# nolleblink2013.net
KiCad netlist of a schematic drawn in EAGLE
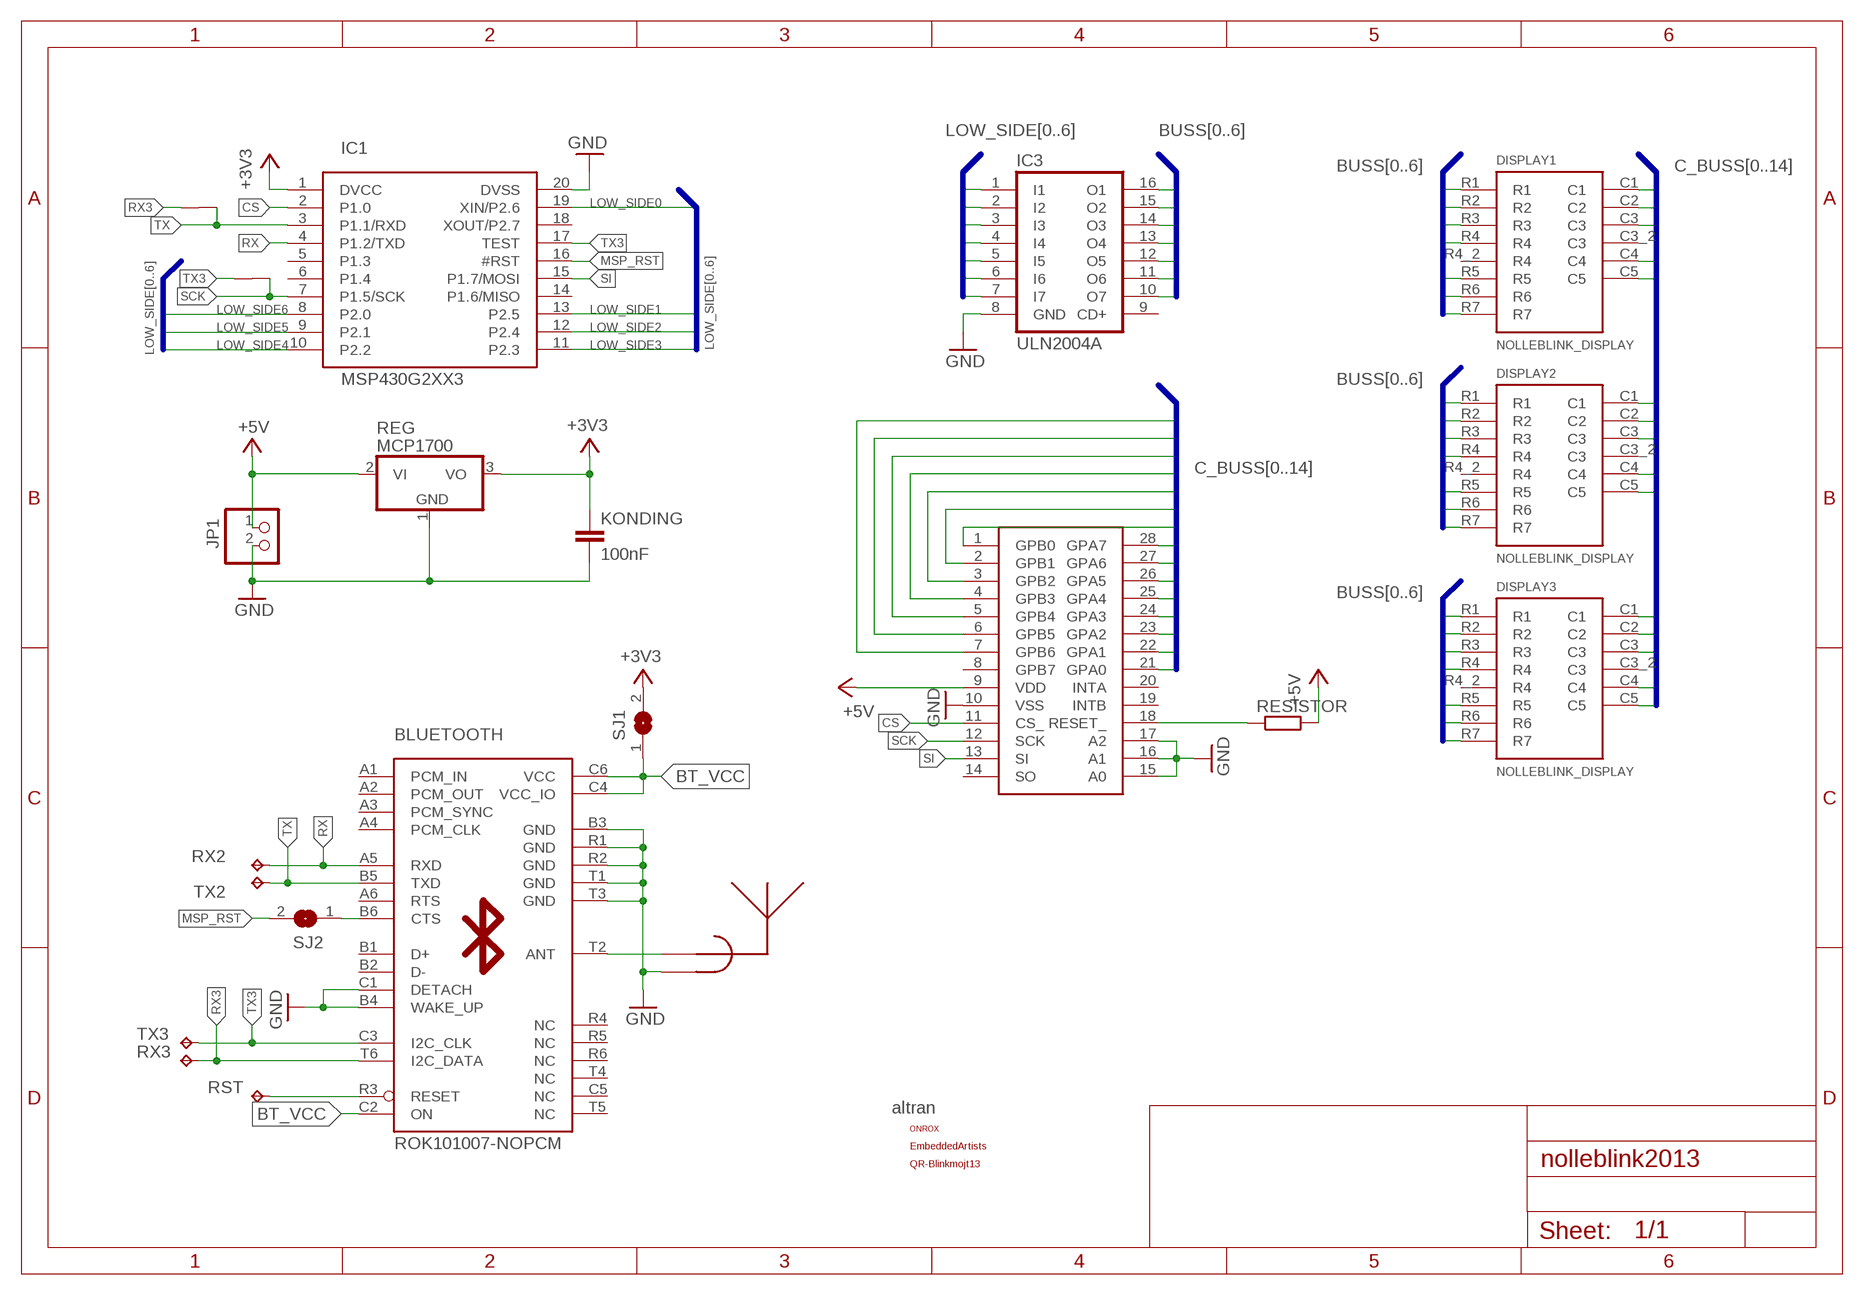
[diagram p0: schematic, sheet 1]

(export (version "E")
  (design (tool "Eeschema 10.0.6"))
  (components
    (comp (ref "BLUETOOTH")
      (value "ROK101007-NOPCM")
      (footprint "eagle-import:ROK101007_NOPCM")
      (libsource (lib "eagle-import") (part "ROK101007-NOPCM"))
    )
    (comp (ref "DISPLAY1")
      (value "NOLLEBLINK_DISPLAY")
      (footprint "eagle-import:KINGBRIGHT_TA12-11EWA")
      (libsource (lib "eagle-import") (part "NOLLEBLINK_DISPLAY"))
    )
    (comp (ref "DISPLAY2")
      (value "NOLLEBLINK_DISPLAY")
      (footprint "eagle-import:KINGBRIGHT_TA12-11EWA")
      (libsource (lib "eagle-import") (part "NOLLEBLINK_DISPLAY"))
    )
    (comp (ref "DISPLAY3")
      (value "NOLLEBLINK_DISPLAY")
      (footprint "eagle-import:KINGBRIGHT_TA12-11EWA")
      (libsource (lib "eagle-import") (part "NOLLEBLINK_DISPLAY"))
    )
    (comp (ref "IC1")
      (value "MSP430G2XX3")
      (footprint "eagle-import:N20")
      (libsource (lib "eagle-import") (part "MSP430G2XX3"))
    )
    (comp (ref "IC2")
      (value "MCPS23S17")
      (footprint "eagle-import:MCP23S17")
      (libsource (lib "eagle-import") (part "MCPS23S17"))
    )
    (comp (ref "IC3")
      (value "ULN2004A")
      (footprint "eagle-import:DIL16")
      (libsource (lib "eagle-import") (part "ULN2004AN"))
    )
    (comp (ref "JP1")
      (value "PINHD-1X2")
      (footprint "eagle-import:1X02")
      (libsource (lib "eagle-import") (part "PINHD-1X2"))
    )
    (comp (ref "KONDING")
      (value "100nF")
      (footprint "eagle-import:C050-030X075")
      (libsource (lib "eagle-import") (part "C-EU050-030X075"))
    )
    (comp (ref "REG")
      (value "MCP1700")
      (footprint "eagle-import:TO92_REGULATOR")
      (libsource (lib "eagle-import") (part "MCP_REGULATOR"))
    )
    (comp (ref "RESISTOR")
      (value "R-EU_0207/10")
      (footprint "eagle-import:0207_10")
      (libsource (lib "eagle-import") (part "R-EU_0207/10"))
    )
    (comp (ref "RST")
      (value "TPTP12SQ")
      (footprint "eagle-import:TP12SQ")
      (libsource (lib "eagle-import") (part "TPTP12SQ"))
    )
    (comp (ref "RX2")
      (value "TPTP20SQ")
      (footprint "eagle-import:TP20SQ")
      (libsource (lib "eagle-import") (part "TPTP20SQ"))
    )
    (comp (ref "RX3")
      (value "TPTP12SQ")
      (footprint "eagle-import:TP12SQ")
      (libsource (lib "eagle-import") (part "TPTP12SQ"))
    )
    (comp (ref "SJ1") (value "SJ") (footprint "eagle-import:SJ") (libsource (lib "eagle-import") (part "SJ")))
    (comp (ref "SJ2") (value "SJ") (footprint "eagle-import:SJ") (libsource (lib "eagle-import") (part "SJ")))
    (comp (ref "TX2")
      (value "TPTP20SQ")
      (footprint "eagle-import:TP20SQ")
      (libsource (lib "eagle-import") (part "TPTP20SQ"))
    )
    (comp (ref "TX3")
      (value "TPTP12SQ")
      (footprint "eagle-import:TP12SQ")
      (libsource (lib "eagle-import") (part "TPTP12SQ"))
    )
    (comp (ref "U$1")
      (value "ALTRAN")
      (footprint "eagle-import:ALTRAN")
      (libsource (lib "eagle-import") (part "ALTRAN"))
    )
    (comp (ref "U$2")
      (value "ONROX")
      (footprint "eagle-import:ONROX")
      (libsource (lib "eagle-import") (part "ONROX"))
    )
    (comp (ref "U$3")
      (value "INV_F_24")
      (footprint "eagle-import:INV_F_ANTENNA")
      (libsource (lib "eagle-import") (part "INV_F_24"))
    )
    (comp (ref "U$4")
      (value "EMBEDDEDARTISTS")
      (footprint "eagle-import:EMBEDDEDARTISTS")
      (libsource (lib "eagle-import") (part "EMBEDDEDARTISTS"))
    )
    (comp (ref "U$5")
      (value "JUNCTION")
      (footprint "eagle-import:JUNCTION")
      (libsource (lib "eagle-import") (part "JUNCTION"))
    )
    (comp (ref "U$6")
      (value "JUNCTION")
      (footprint "eagle-import:JUNCTION")
      (libsource (lib "eagle-import") (part "JUNCTION"))
    )
    (comp (ref "U$7")
      (value "BLINKMOJT13")
      (footprint "eagle-import:BLINKMOJT13")
      (libsource (lib "eagle-import") (part "BLINKMOJT13"))
    )
  )
  (nets
    (net (code "1") (name "+3V3") (class "Default")
      (node (ref "IC1") (pin "1") (pinfunction "DVCC_1") (pintype "bidirectional"))
      (node (ref "KONDING") (pin "1") (pinfunction "1_1") (pintype "passive"))
      (node (ref "REG") (pin "3") (pinfunction "VO_3") (pintype "passive"))
      (node (ref "SJ1") (pin "2") (pinfunction "2_2") (pintype "passive"))
    )
    (net (code "2") (name "+5V") (class "Default")
      (node (ref "IC2") (pin "9") (pinfunction "VDD_9") (pintype "bidirectional"))
      (node (ref "JP1") (pin "1") (pinfunction "1_1") (pintype "passive"))
      (node (ref "REG") (pin "2") (pinfunction "VI_2") (pintype "input"))
      (node (ref "RESISTOR") (pin "2") (pinfunction "2_2") (pintype "passive"))
    )
    (net (code "3") (name "/BUSS0") (class "Default")
      (node (ref "DISPLAY1") (pin "R1") (pinfunction "R1_R1") (pintype "bidirectional"))
      (node (ref "DISPLAY2") (pin "R1") (pinfunction "R1_R1") (pintype "bidirectional"))
      (node (ref "DISPLAY3") (pin "R1") (pinfunction "R1_R1") (pintype "bidirectional"))
      (node (ref "IC3") (pin "16") (pinfunction "O1_16") (pintype "open_collector"))
    )
    (net (code "4") (name "/BUSS1") (class "Default")
      (node (ref "DISPLAY1") (pin "R2") (pinfunction "R2_R2") (pintype "bidirectional"))
      (node (ref "DISPLAY2") (pin "R2") (pinfunction "R2_R2") (pintype "bidirectional"))
      (node (ref "DISPLAY3") (pin "R2") (pinfunction "R2_R2") (pintype "bidirectional"))
      (node (ref "IC3") (pin "15") (pinfunction "O2_15") (pintype "open_collector"))
    )
    (net (code "5") (name "/BUSS2") (class "Default")
      (node (ref "DISPLAY1") (pin "R3") (pinfunction "R3_R3") (pintype "bidirectional"))
      (node (ref "DISPLAY2") (pin "R3") (pinfunction "R3_R3") (pintype "bidirectional"))
      (node (ref "DISPLAY3") (pin "R3") (pinfunction "R3_R3") (pintype "bidirectional"))
      (node (ref "IC3") (pin "14") (pinfunction "O3_14") (pintype "open_collector"))
    )
    (net (code "6") (name "/BUSS3") (class "Default")
      (node (ref "DISPLAY1") (pin "R4") (pinfunction "R4_R4") (pintype "bidirectional"))
      (node (ref "DISPLAY2") (pin "R4") (pinfunction "R4_R4") (pintype "bidirectional"))
      (node (ref "DISPLAY3") (pin "R4") (pinfunction "R4_R4") (pintype "bidirectional"))
      (node (ref "IC3") (pin "13") (pinfunction "O4_13") (pintype "open_collector"))
    )
    (net (code "7") (name "/BUSS4") (class "Default")
      (node (ref "DISPLAY1") (pin "R5") (pinfunction "R5_R5") (pintype "bidirectional"))
      (node (ref "DISPLAY2") (pin "R5") (pinfunction "R5_R5") (pintype "bidirectional"))
      (node (ref "DISPLAY3") (pin "R5") (pinfunction "R5_R5") (pintype "bidirectional"))
      (node (ref "IC3") (pin "12") (pinfunction "O5_12") (pintype "open_collector"))
    )
    (net (code "8") (name "/BUSS5") (class "Default")
      (node (ref "DISPLAY1") (pin "R6") (pinfunction "R6_R6") (pintype "bidirectional"))
      (node (ref "DISPLAY2") (pin "R6") (pinfunction "R6_R6") (pintype "bidirectional"))
      (node (ref "DISPLAY3") (pin "R6") (pinfunction "R6_R6") (pintype "bidirectional"))
      (node (ref "IC3") (pin "11") (pinfunction "O6_11") (pintype "open_collector"))
    )
    (net (code "9") (name "/BUSS6") (class "Default")
      (node (ref "DISPLAY1") (pin "R7") (pinfunction "R7_R7") (pintype "bidirectional"))
      (node (ref "DISPLAY2") (pin "R7") (pinfunction "R7_R7") (pintype "bidirectional"))
      (node (ref "DISPLAY3") (pin "R7") (pinfunction "R7_R7") (pintype "bidirectional"))
      (node (ref "IC3") (pin "10") (pinfunction "O7_10") (pintype "open_collector"))
    )
    (net (code "11") (name "/C_BUSS0") (class "Default")
      (node (ref "DISPLAY1") (pin "C1") (pinfunction "C1_C1") (pintype "bidirectional"))
      (node (ref "IC2") (pin "21") (pinfunction "GPA0_21") (pintype "bidirectional"))
    )
    (net (code "12") (name "/C_BUSS1") (class "Default")
      (node (ref "DISPLAY1") (pin "C2") (pinfunction "C2_C2") (pintype "bidirectional"))
      (node (ref "IC2") (pin "22") (pinfunction "GPA1_22") (pintype "bidirectional"))
    )
    (net (code "13") (name "/C_BUSS2") (class "Default")
      (node (ref "DISPLAY1") (pin "C3") (pinfunction "C3_C3") (pintype "bidirectional"))
      (node (ref "IC2") (pin "23") (pinfunction "GPA2_23") (pintype "bidirectional"))
    )
    (net (code "14") (name "/C_BUSS3") (class "Default")
      (node (ref "DISPLAY1") (pin "C4") (pinfunction "C4_C4") (pintype "bidirectional"))
      (node (ref "IC2") (pin "24") (pinfunction "GPA3_24") (pintype "bidirectional"))
    )
    (net (code "15") (name "/C_BUSS4") (class "Default")
      (node (ref "DISPLAY1") (pin "C5") (pinfunction "C5_C5") (pintype "bidirectional"))
      (node (ref "IC2") (pin "25") (pinfunction "GPA4_25") (pintype "bidirectional"))
    )
    (net (code "16") (name "/C_BUSS5") (class "Default")
      (node (ref "DISPLAY2") (pin "C1") (pinfunction "C1_C1") (pintype "bidirectional"))
      (node (ref "IC2") (pin "26") (pinfunction "GPA5_26") (pintype "bidirectional"))
    )
    (net (code "17") (name "/C_BUSS6") (class "Default")
      (node (ref "DISPLAY2") (pin "C2") (pinfunction "C2_C2") (pintype "bidirectional"))
      (node (ref "IC2") (pin "27") (pinfunction "GPA6_27") (pintype "bidirectional"))
    )
    (net (code "18") (name "/C_BUSS7") (class "Default")
      (node (ref "DISPLAY2") (pin "C3") (pinfunction "C3_C3") (pintype "bidirectional"))
      (node (ref "IC2") (pin "28") (pinfunction "GPA7_28") (pintype "bidirectional"))
    )
    (net (code "19") (name "/C_BUSS8") (class "Default")
      (node (ref "DISPLAY2") (pin "C4") (pinfunction "C4_C4") (pintype "bidirectional"))
      (node (ref "IC2") (pin "1") (pinfunction "GPB0_1") (pintype "bidirectional"))
    )
    (net (code "20") (name "/C_BUSS9") (class "Default")
      (node (ref "DISPLAY2") (pin "C5") (pinfunction "C5_C5") (pintype "bidirectional"))
      (node (ref "IC2") (pin "2") (pinfunction "GPB1_2") (pintype "bidirectional"))
    )
    (net (code "21") (name "/C_BUSS10") (class "Default")
      (node (ref "DISPLAY3") (pin "C1") (pinfunction "C1_C1") (pintype "bidirectional"))
      (node (ref "IC2") (pin "3") (pinfunction "GPB2_3") (pintype "bidirectional"))
    )
    (net (code "22") (name "/C_BUSS11") (class "Default")
      (node (ref "DISPLAY3") (pin "C2") (pinfunction "C2_C2") (pintype "bidirectional"))
      (node (ref "IC2") (pin "4") (pinfunction "GPB3_4") (pintype "bidirectional"))
    )
    (net (code "23") (name "/C_BUSS12") (class "Default")
      (node (ref "DISPLAY3") (pin "C3") (pinfunction "C3_C3") (pintype "bidirectional"))
      (node (ref "IC2") (pin "5") (pinfunction "GPB4_5") (pintype "bidirectional"))
    )
    (net (code "24") (name "/C_BUSS13") (class "Default")
      (node (ref "DISPLAY3") (pin "C4") (pinfunction "C4_C4") (pintype "bidirectional"))
      (node (ref "IC2") (pin "6") (pinfunction "GPB5_6") (pintype "bidirectional"))
    )
    (net (code "25") (name "/C_BUSS14") (class "Default")
      (node (ref "DISPLAY3") (pin "C5") (pinfunction "C5_C5") (pintype "bidirectional"))
      (node (ref "IC2") (pin "7") (pinfunction "GPB6_7") (pintype "bidirectional"))
    )
    (net (code "27") (name "/LOW_SIDE0") (class "Default")
      (node (ref "IC1") (pin "19") (pinfunction "XIN/P2.6_19") (pintype "bidirectional"))
      (node (ref "IC3") (pin "7") (pinfunction "I7_7") (pintype "input"))
    )
    (net (code "28") (name "/LOW_SIDE1") (class "Default")
      (node (ref "IC1") (pin "13") (pinfunction "P2.5_13") (pintype "bidirectional"))
      (node (ref "IC3") (pin "6") (pinfunction "I6_6") (pintype "input"))
    )
    (net (code "29") (name "/LOW_SIDE2") (class "Default")
      (node (ref "IC1") (pin "12") (pinfunction "P2.4_12") (pintype "bidirectional"))
      (node (ref "IC3") (pin "5") (pinfunction "I5_5") (pintype "input"))
    )
    (net (code "30") (name "/LOW_SIDE3") (class "Default")
      (node (ref "IC1") (pin "11") (pinfunction "P2.3_11") (pintype "bidirectional"))
      (node (ref "IC3") (pin "4") (pinfunction "I4_4") (pintype "input"))
    )
    (net (code "31") (name "/LOW_SIDE4") (class "Default")
      (node (ref "IC1") (pin "10") (pinfunction "P2.2_10") (pintype "bidirectional"))
      (node (ref "IC3") (pin "3") (pinfunction "I3_3") (pintype "input"))
    )
    (net (code "32") (name "/LOW_SIDE5") (class "Default")
      (node (ref "IC1") (pin "9") (pinfunction "P2.1_9") (pintype "bidirectional"))
      (node (ref "IC3") (pin "2") (pinfunction "I2_2") (pintype "input"))
    )
    (net (code "33") (name "/LOW_SIDE6") (class "Default")
      (node (ref "IC1") (pin "8") (pinfunction "P2.0_8") (pintype "bidirectional"))
      (node (ref "IC3") (pin "1") (pinfunction "I1_1") (pintype "input"))
    )
    (net (code "35") (name "BT_VCC") (class "Default")
      (node (ref "BLUETOOTH") (pin "C2") (pinfunction "ON_C2") (pintype "bidirectional"))
      (node (ref "BLUETOOTH") (pin "C4") (pinfunction "VCC_IO_C4") (pintype "bidirectional"))
      (node (ref "BLUETOOTH") (pin "C6") (pinfunction "VCC_C6") (pintype "bidirectional"))
      (node (ref "SJ1") (pin "1") (pinfunction "1_1") (pintype "passive"))
    )
    (net (code "36") (name "CS") (class "Default")
      (node (ref "IC1") (pin "2") (pinfunction "P1.0_2") (pintype "bidirectional"))
      (node (ref "IC2") (pin "11") (pinfunction "CS__11") (pintype "bidirectional"))
    )
    (net (code "37") (name "GND") (class "Default")
      (node (ref "BLUETOOTH") (pin "B3") (pinfunction "GND_B3") (pintype "bidirectional"))
      (node (ref "BLUETOOTH") (pin "B4") (pinfunction "WAKE_UP_B4") (pintype "bidirectional"))
      (node (ref "BLUETOOTH") (pin "C1") (pinfunction "DETACH_C1") (pintype "bidirectional"))
      (node (ref "BLUETOOTH") (pin "R1") (pinfunction "GND_R1") (pintype "bidirectional"))
      (node (ref "BLUETOOTH") (pin "R2") (pinfunction "GND_R2") (pintype "bidirectional"))
      (node (ref "BLUETOOTH") (pin "T1") (pinfunction "GND_T1") (pintype "bidirectional"))
      (node (ref "BLUETOOTH") (pin "T3") (pinfunction "GND_T3") (pintype "bidirectional"))
      (node (ref "IC1") (pin "20") (pinfunction "DVSS_20") (pintype "bidirectional"))
      (node (ref "IC2") (pin "10") (pinfunction "VSS_10") (pintype "bidirectional"))
      (node (ref "IC2") (pin "15") (pinfunction "A0_15") (pintype "bidirectional"))
      (node (ref "IC2") (pin "16") (pinfunction "A1_16") (pintype "bidirectional"))
      (node (ref "IC2") (pin "17") (pinfunction "A2_17") (pintype "bidirectional"))
      (node (ref "IC3") (pin "8") (pinfunction "GND_8") (pintype "power_in"))
      (node (ref "JP1") (pin "2") (pinfunction "2_2") (pintype "passive"))
      (node (ref "KONDING") (pin "2") (pinfunction "2_2") (pintype "passive"))
      (node (ref "REG") (pin "1") (pinfunction "GND_1") (pintype "passive"))
      (node (ref "U$3") (pin "GND") (pinfunction "GND_GND") (pintype "bidirectional"))
    )
    (net (code "38") (name "MSP_RST") (class "Default")
      (node (ref "IC1") (pin "16") (pinfunction "#RST_16") (pintype "bidirectional"))
      (node (ref "SJ2") (pin "2") (pinfunction "2_2") (pintype "passive"))
    )
    (net (code "39") (name "Net-(BLUETOOTH-ANT)") (class "Default")
      (node (ref "BLUETOOTH") (pin "T2") (pinfunction "ANT_T2") (pintype "bidirectional"))
      (node (ref "U$3") (pin "FEED") (pinfunction "RF_FEED") (pintype "bidirectional"))
    )
    (net (code "40") (name "Net-(BLUETOOTH-CTS)") (class "Default")
      (node (ref "BLUETOOTH") (pin "B6") (pinfunction "CTS_B6") (pintype "bidirectional"))
      (node (ref "SJ2") (pin "1") (pinfunction "1_1") (pintype "passive"))
    )
    (net (code "41") (name "Net-(BLUETOOTH-RESET)") (class "Default")
      (node (ref "BLUETOOTH") (pin "R3") (pinfunction "RESET_R3") (pintype "bidirectional"))
      (node (ref "RST") (pin "TP") (pinfunction "TP_TP") (pintype "input"))
    )
    (net (code "42") (name "Net-(IC2-RESET_)") (class "Default")
      (node (ref "IC2") (pin "18") (pinfunction "RESET__18") (pintype "bidirectional"))
      (node (ref "RESISTOR") (pin "1") (pinfunction "1_1") (pintype "passive"))
    )
    (net (code "43") (name "RX") (class "Default")
      (node (ref "BLUETOOTH") (pin "A5") (pinfunction "RXD_A5") (pintype "bidirectional"))
      (node (ref "IC1") (pin "4") (pinfunction "P1.2/TXD_4") (pintype "bidirectional"))
      (node (ref "RX2") (pin "TP") (pinfunction "TP_TP") (pintype "input"))
    )
    (net (code "44") (name "RX3") (class "Default")
      (node (ref "BLUETOOTH") (pin "T6") (pinfunction "I2C_DATA_T6") (pintype "bidirectional"))
      (node (ref "RX3") (pin "TP") (pinfunction "TP_TP") (pintype "input"))
      (node (ref "U$6") (pin "P$2") (pinfunction "P$2_P$2") (pintype "bidirectional"))
    )
    (net (code "45") (name "SCK") (class "Default")
      (node (ref "IC1") (pin "7") (pinfunction "P1.5/SCK_7") (pintype "bidirectional"))
      (node (ref "IC2") (pin "12") (pinfunction "SCK_12") (pintype "bidirectional"))
      (node (ref "U$5") (pin "P$1") (pinfunction "P$1_P$1") (pintype "bidirectional"))
    )
    (net (code "46") (name "SI") (class "Default")
      (node (ref "IC1") (pin "15") (pinfunction "P1.7/MOSI_15") (pintype "bidirectional"))
      (node (ref "IC2") (pin "13") (pinfunction "SI_13") (pintype "bidirectional"))
    )
    (net (code "47") (name "TX") (class "Default")
      (node (ref "BLUETOOTH") (pin "B5") (pinfunction "TXD_B5") (pintype "bidirectional"))
      (node (ref "IC1") (pin "3") (pinfunction "P1.1/RXD_3") (pintype "bidirectional"))
      (node (ref "TX2") (pin "TP") (pinfunction "TP_TP") (pintype "input"))
      (node (ref "U$6") (pin "P$1") (pinfunction "P$1_P$1") (pintype "bidirectional"))
    )
    (net (code "48") (name "TX3") (class "Default")
      (node (ref "BLUETOOTH") (pin "C3") (pinfunction "I2C_CLK_C3") (pintype "bidirectional"))
      (node (ref "IC1") (pin "17") (pinfunction "TEST_17") (pintype "bidirectional"))
      (node (ref "TX3") (pin "TP") (pinfunction "TP_TP") (pintype "input"))
      (node (ref "U$5") (pin "P$2") (pinfunction "P$2_P$2") (pintype "bidirectional"))
    )
    (net (code "49") (name "unconnected-(BLUETOOTH-D+-PadB1)") (class "Default")
      (node (ref "BLUETOOTH") (pin "B1") (pinfunction "D+_B1") (pintype "bidirectional"))
    )
    (net (code "50") (name "unconnected-(BLUETOOTH-D--PadB2)") (class "Default")
      (node (ref "BLUETOOTH") (pin "B2") (pinfunction "D-_B2") (pintype "bidirectional"))
    )
    (net (code "51") (name "unconnected-(BLUETOOTH-NC-PadC5)") (class "Default")
      (node (ref "BLUETOOTH") (pin "C5") (pinfunction "NC_C5") (pintype "bidirectional"))
    )
    (net (code "52") (name "unconnected-(BLUETOOTH-NC-PadR4)") (class "Default")
      (node (ref "BLUETOOTH") (pin "R4") (pinfunction "NC_R4") (pintype "bidirectional"))
    )
    (net (code "53") (name "unconnected-(BLUETOOTH-NC-PadR5)") (class "Default")
      (node (ref "BLUETOOTH") (pin "R5") (pinfunction "NC_R5") (pintype "bidirectional"))
    )
    (net (code "54") (name "unconnected-(BLUETOOTH-NC-PadR6)") (class "Default")
      (node (ref "BLUETOOTH") (pin "R6") (pinfunction "NC_R6") (pintype "bidirectional"))
    )
    (net (code "55") (name "unconnected-(BLUETOOTH-NC-PadT4)") (class "Default")
      (node (ref "BLUETOOTH") (pin "T4") (pinfunction "NC_T4") (pintype "bidirectional"))
    )
    (net (code "56") (name "unconnected-(BLUETOOTH-NC-PadT5)") (class "Default")
      (node (ref "BLUETOOTH") (pin "T5") (pinfunction "NC_T5") (pintype "bidirectional"))
    )
    (net (code "57") (name "unconnected-(BLUETOOTH-PCM_CLK-PadA4)") (class "Default")
      (node (ref "BLUETOOTH") (pin "A4") (pinfunction "PCM_CLK_A4") (pintype "bidirectional"))
    )
    (net (code "58") (name "unconnected-(BLUETOOTH-PCM_IN-PadA1)") (class "Default")
      (node (ref "BLUETOOTH") (pin "A1") (pinfunction "PCM_IN_A1") (pintype "bidirectional"))
    )
    (net (code "59") (name "unconnected-(BLUETOOTH-PCM_OUT-PadA2)") (class "Default")
      (node (ref "BLUETOOTH") (pin "A2") (pinfunction "PCM_OUT_A2") (pintype "bidirectional"))
    )
    (net (code "60") (name "unconnected-(BLUETOOTH-PCM_SYNC-PadA3)") (class "Default")
      (node (ref "BLUETOOTH") (pin "A3") (pinfunction "PCM_SYNC_A3") (pintype "bidirectional"))
    )
    (net (code "61") (name "unconnected-(BLUETOOTH-RTS-PadA6)") (class "Default")
      (node (ref "BLUETOOTH") (pin "A6") (pinfunction "RTS_A6") (pintype "bidirectional"))
    )
    (net (code "62") (name "unconnected-(DISPLAY1-C3-PadC3_2)") (class "Default")
      (node (ref "DISPLAY1") (pin "C3_2") (pinfunction "C3_C3_2") (pintype "bidirectional"))
    )
    (net (code "63") (name "unconnected-(DISPLAY1-R4-PadR4_2)") (class "Default")
      (node (ref "DISPLAY1") (pin "R4_2") (pinfunction "R4_R4_2") (pintype "bidirectional"))
    )
    (net (code "64") (name "unconnected-(DISPLAY2-C3-PadC3_2)") (class "Default")
      (node (ref "DISPLAY2") (pin "C3_2") (pinfunction "C3_C3_2") (pintype "bidirectional"))
    )
    (net (code "65") (name "unconnected-(DISPLAY2-R4-PadR4_2)") (class "Default")
      (node (ref "DISPLAY2") (pin "R4_2") (pinfunction "R4_R4_2") (pintype "bidirectional"))
    )
    (net (code "66") (name "unconnected-(DISPLAY3-C3-PadC3_2)") (class "Default")
      (node (ref "DISPLAY3") (pin "C3_2") (pinfunction "C3_C3_2") (pintype "bidirectional"))
    )
    (net (code "67") (name "unconnected-(DISPLAY3-R4-PadR4_2)") (class "Default")
      (node (ref "DISPLAY3") (pin "R4_2") (pinfunction "R4_R4_2") (pintype "bidirectional"))
    )
    (net (code "68") (name "unconnected-(IC1-P1.3-Pad5)") (class "Default")
      (node (ref "IC1") (pin "5") (pinfunction "P1.3_5") (pintype "bidirectional"))
    )
    (net (code "69") (name "unconnected-(IC1-P1.4-Pad6)") (class "Default")
      (node (ref "IC1") (pin "6") (pinfunction "P1.4_6") (pintype "bidirectional"))
    )
    (net (code "70") (name "unconnected-(IC1-P1.6{slash}MISO-Pad14)") (class "Default")
      (node (ref "IC1") (pin "14") (pinfunction "P1.6/MISO_14") (pintype "bidirectional"))
    )
    (net (code "71") (name "unconnected-(IC1-XOUT{slash}P2.7-Pad18)") (class "Default")
      (node (ref "IC1") (pin "18") (pinfunction "XOUT/P2.7_18") (pintype "bidirectional"))
    )
    (net (code "72") (name "unconnected-(IC2-GPB7-Pad8)") (class "Default")
      (node (ref "IC2") (pin "8") (pinfunction "GPB7_8") (pintype "bidirectional"))
    )
    (net (code "73") (name "unconnected-(IC2-INTA-Pad20)") (class "Default")
      (node (ref "IC2") (pin "20") (pinfunction "INTA_20") (pintype "bidirectional"))
    )
    (net (code "74") (name "unconnected-(IC2-INTB-Pad19)") (class "Default")
      (node (ref "IC2") (pin "19") (pinfunction "INTB_19") (pintype "bidirectional"))
    )
    (net (code "75") (name "unconnected-(IC2-SO-Pad14)") (class "Default")
      (node (ref "IC2") (pin "14") (pinfunction "SO_14") (pintype "bidirectional"))
    )
    (net (code "76") (name "unconnected-(IC3-CD+-Pad9)") (class "Default")
      (node (ref "IC3") (pin "9") (pinfunction "CD+_9") (pintype "passive"))
    )
  )
)
